# pinheader.net
KiCad netlist of a schematic drawn in Altium Designer
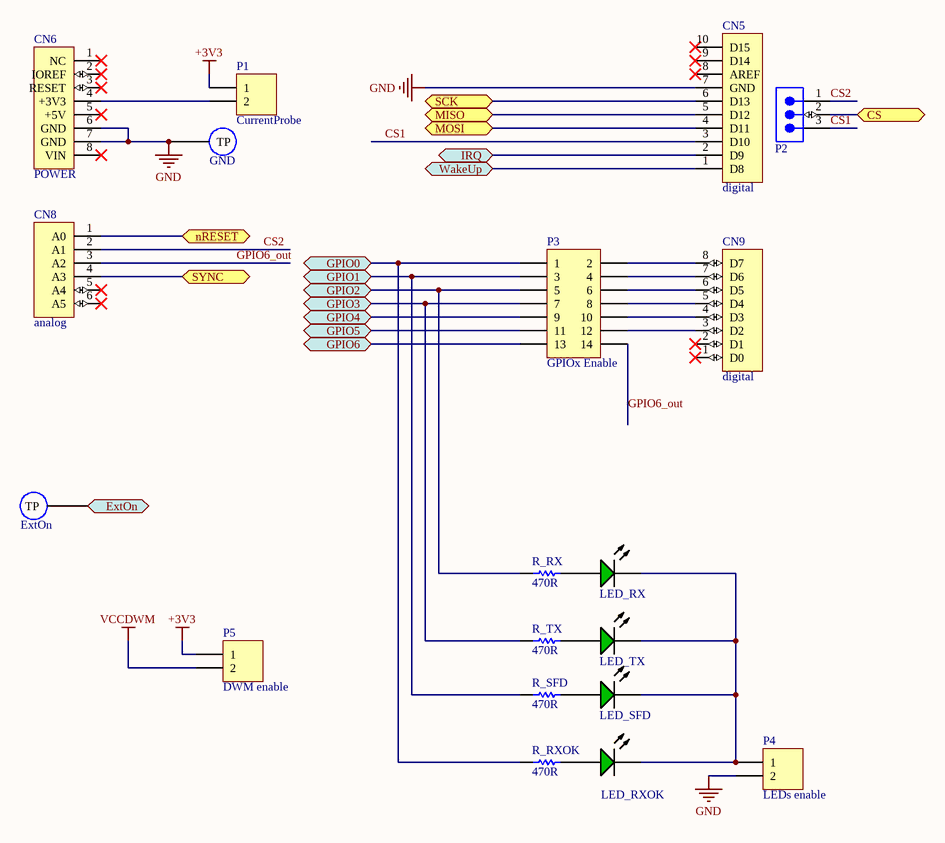
[diagram p0: pinheader.SchDoc]

(export (version "E")
  (design (tool "Eeschema 10.0.6"))
  (components
    (comp (ref "CN5")
      (value "digital")
      (footprint "HDR1X10")
      (description "Header, 10-Pin")
      (fields (field (name "PUBLISHER") "Altium Limited"))
      (libsource (lib "Miscellaneous Connectors") (part "Header 10"))
    )
    (comp (ref "CN6")
      (value "POWER")
      (footprint "HDR1X8")
      (description "Header, 8-Pin")
      (fields (field (name "PUBLISHER") "Altium Limited"))
      (libsource (lib "") (part "Header 8_1"))
    )
    (comp (ref "CN8")
      (value "analog")
      (footprint "HDR1X6")
      (description "Header, 6-Pin")
      (fields (field (name "PUBLISHER") "Altium Limited"))
      (libsource (lib "Miscellaneous Connectors") (part "Header 6"))
    )
    (comp (ref "CN9")
      (value "digital")
      (footprint "HDR1X8")
      (description "Header, 8-Pin")
      (fields (field (name "PUBLISHER") "Altium Limited"))
      (libsource (lib "Miscellaneous Connectors") (part "Header 8"))
    )
    (comp (ref "ExtOn")
      (value "Component_1")
      (footprint "KSTN-5000")
      (description "test point")
      (libsource (lib "testpoint") (part "Component_1"))
    )
    (comp (ref "GND")
      (value "Component_1")
      (footprint "KSTN-5000")
      (description "test point")
      (libsource (lib "testpoint") (part "Component_1"))
    )
    (comp (ref "LED_RX")
      (value "APG1608CGKC/T")
      (footprint "KING-LED0603-25-GREEN_V")
      (description "LED, SMT, 0603(1608), 0.25mm Thickness, Green")
      (libsource (lib "Altium Content Vault") (part "CMP-0239-00001-1"))
    )
    (comp (ref "LED_RXOK")
      (value "APG1608CGKC/T")
      (footprint "KING-LED0603-25-GREEN_V")
      (description "LED, SMT, 0603(1608), 0.25mm Thickness, Green")
      (libsource (lib "Altium Content Vault") (part "CMP-0239-00001-1"))
    )
    (comp (ref "LED_SFD")
      (value "APG1608CGKC/T")
      (footprint "KING-LED0603-25-GREEN_V")
      (description "LED, SMT, 0603(1608), 0.25mm Thickness, Green")
      (libsource (lib "Altium Content Vault") (part "CMP-0239-00001-1"))
    )
    (comp (ref "LED_TX")
      (value "APG1608CGKC/T")
      (footprint "KING-LED0603-25-GREEN_V")
      (description "LED, SMT, 0603(1608), 0.25mm Thickness, Green")
      (libsource (lib "Altium Content Vault") (part "CMP-0239-00001-1"))
    )
    (comp (ref "P1")
      (value "CurrentProbe")
      (footprint "HDR1X2H")
      (description "Header, 2-Pin, Right Angle")
      (fields (field (name "PUBLISHER") "Altium Limited"))
      (libsource (lib "Miscellaneous Connectors") (part "Header 2H"))
    )
    (comp (ref "P2")
      (value "Through-hole")
      (footprint "SMTC-MTSW-103-08-X-S-229-RA")
      (fields (field (name "MANUFACTURER") "Samtec") (field (name "PARTNUMBER") "MTSW-103-08-G-S-229-RA"))
      (libsource (lib "Altium Content Vault") (part "CMP-1024-00100-1"))
    )
    (comp (ref "P3")
      (value "GPIOx Enable")
      (footprint "HDR2X7")
      (description "Header, 7-Pin, Dual row")
      (fields (field (name "PUBLISHER") "Altium Limited"))
      (libsource (lib "Miscellaneous Connectors") (part "Header 7X2"))
    )
    (comp (ref "P4")
      (value "LEDs enable")
      (footprint "HDR1X2")
      (description "Header, 2-Pin")
      (fields (field (name "PUBLISHER") "Altium Limited"))
      (libsource (lib "Miscellaneous Connectors") (part "Header 2"))
    )
    (comp (ref "P5")
      (value "DWM enable")
      (footprint "HDR1X2")
      (description "Header, 2-Pin")
      (fields (field (name "PUBLISHER") "Altium Limited"))
      (libsource (lib "Miscellaneous Connectors") (part "Header 2"))
    )
    (comp (ref "R_RX")
      (value "470R")
      (footprint "RESC0603(1608)_L")
      (description "470R 0.1W 1% 0603 (1608 Metric)  SMD")
      (fields (field (name "POWER") "0.1 W") (field (name "TOLERANCE") "1 %"))
      (libsource (lib "Altium Content Vault") (part "RES"))
    )
    (comp (ref "R_RXOK")
      (value "470R")
      (footprint "RESC0603(1608)_L")
      (description "470R 0.1W 1% 0603 (1608 Metric)  SMD")
      (fields (field (name "POWER") "0.1 W") (field (name "TOLERANCE") "1 %"))
      (libsource (lib "Altium Content Vault") (part "RES"))
    )
    (comp (ref "R_SFD")
      (value "470R")
      (footprint "RESC0603(1608)_L")
      (description "470R 0.1W 1% 0603 (1608 Metric)  SMD")
      (fields (field (name "POWER") "0.1 W") (field (name "TOLERANCE") "1 %"))
      (libsource (lib "Altium Content Vault") (part "RES"))
    )
    (comp (ref "R_TX")
      (value "470R")
      (footprint "RESC0603(1608)_L")
      (description "470R 0.1W 1% 0603 (1608 Metric)  SMD")
      (fields (field (name "POWER") "0.1 W") (field (name "TOLERANCE") "1 %"))
      (libsource (lib "Altium Content Vault") (part "RES"))
    )
  )
  (nets
    (net (code "1") (name "+3V3") (class "Default")
      (node (ref "P1") (pin "1") (pinfunction "1_1") (pintype "passive"))
      (node (ref "P5") (pin "1") (pinfunction "1_1") (pintype "passive"))
    )
    (net (code "2") (name "/CS") (class "Default")
      (node (ref "P2") (pin "2") (pinfunction "2_2") (pintype "bidirectional"))
    )
    (net (code "3") (name "/CS1") (class "Default")
      (node (ref "CN5") (pin "3") (pinfunction "D10_3") (pintype "passive"))
      (node (ref "P2") (pin "3") (pinfunction "3_3") (pintype "passive"))
    )
    (net (code "4") (name "/CS2") (class "Default")
      (node (ref "CN8") (pin "2") (pinfunction "A1_2") (pintype "passive"))
      (node (ref "P2") (pin "1") (pinfunction "1_1") (pintype "passive"))
    )
    (net (code "5") (name "/ExtOn") (class "Default")
      (node (ref "ExtOn") (pin "1") (pinfunction "TP_1") (pintype "passive"))
    )
    (net (code "6") (name "/GPIO0") (class "Default")
      (node (ref "P3") (pin "1") (pinfunction "1_1") (pintype "passive"))
      (node (ref "R_RXOK") (pin "1") (pinfunction "1_1") (pintype "passive"))
    )
    (net (code "7") (name "/GPIO1") (class "Default")
      (node (ref "P3") (pin "3") (pinfunction "3_3") (pintype "passive"))
      (node (ref "R_SFD") (pin "1") (pinfunction "1_1") (pintype "passive"))
    )
    (net (code "8") (name "/GPIO2") (class "Default")
      (node (ref "P3") (pin "5") (pinfunction "5_5") (pintype "passive"))
      (node (ref "R_RX") (pin "1") (pinfunction "1_1") (pintype "passive"))
    )
    (net (code "9") (name "/GPIO3") (class "Default")
      (node (ref "P3") (pin "7") (pinfunction "7_7") (pintype "passive"))
      (node (ref "R_TX") (pin "1") (pinfunction "1_1") (pintype "passive"))
    )
    (net (code "10") (name "/GPIO4") (class "Default")
      (node (ref "P3") (pin "9") (pinfunction "9_9") (pintype "passive"))
    )
    (net (code "11") (name "/GPIO5") (class "Default")
      (node (ref "P3") (pin "11") (pinfunction "11_11") (pintype "passive"))
    )
    (net (code "12") (name "/GPIO6") (class "Default")
      (node (ref "P3") (pin "13") (pinfunction "13_13") (pintype "passive"))
    )
    (net (code "13") (name "/GPIO6_out") (class "Default")
      (node (ref "CN8") (pin "3") (pinfunction "A2_3") (pintype "passive"))
      (node (ref "P3") (pin "14") (pinfunction "14_14") (pintype "passive"))
    )
    (net (code "14") (name "/IRQ") (class "Default")
      (node (ref "CN5") (pin "2") (pinfunction "D9_2") (pintype "passive"))
    )
    (net (code "15") (name "/MISO") (class "Default")
      (node (ref "CN5") (pin "5") (pinfunction "D12_5") (pintype "passive"))
    )
    (net (code "16") (name "/MOSI") (class "Default")
      (node (ref "CN5") (pin "4") (pinfunction "D11_4") (pintype "passive"))
    )
    (net (code "17") (name "/SCK") (class "Default")
      (node (ref "CN5") (pin "6") (pinfunction "D13_6") (pintype "passive"))
    )
    (net (code "18") (name "/SYNC") (class "Default")
      (node (ref "CN8") (pin "4") (pinfunction "A3_4") (pintype "passive"))
    )
    (net (code "19") (name "/WakeUp") (class "Default")
      (node (ref "CN5") (pin "1") (pinfunction "D8_1") (pintype "passive"))
    )
    (net (code "20") (name "/nRESET") (class "Default")
      (node (ref "CN8") (pin "1") (pinfunction "A0_1") (pintype "passive"))
    )
    (net (code "21") (name "GND") (class "Default")
      (node (ref "CN5") (pin "7") (pinfunction "GND_7") (pintype "passive"))
      (node (ref "CN6") (pin "6") (pinfunction "GND_6") (pintype "passive"))
      (node (ref "CN6") (pin "7") (pinfunction "GND_7") (pintype "passive"))
      (node (ref "GND") (pin "1") (pinfunction "TP_1") (pintype "passive"))
      (node (ref "P4") (pin "2") (pinfunction "2_2") (pintype "passive"))
    )
    (net (code "22") (name "Net-(CN6-+3V3)") (class "Default")
      (node (ref "CN6") (pin "4") (pinfunction "+3V3_4") (pintype "power_in"))
      (node (ref "P1") (pin "2") (pinfunction "2_2") (pintype "passive"))
    )
    (net (code "23") (name "Net-(CN9-D2)") (class "Default")
      (node (ref "CN9") (pin "3") (pinfunction "D2_3") (pintype "bidirectional"))
      (node (ref "P3") (pin "12") (pinfunction "12_12") (pintype "passive"))
    )
    (net (code "24") (name "Net-(CN9-D3)") (class "Default")
      (node (ref "CN9") (pin "4") (pinfunction "D3_4") (pintype "bidirectional"))
      (node (ref "P3") (pin "10") (pinfunction "10_10") (pintype "passive"))
    )
    (net (code "25") (name "Net-(CN9-D4)") (class "Default")
      (node (ref "CN9") (pin "5") (pinfunction "D4_5") (pintype "bidirectional"))
      (node (ref "P3") (pin "8") (pinfunction "8_8") (pintype "passive"))
    )
    (net (code "26") (name "Net-(CN9-D5)") (class "Default")
      (node (ref "CN9") (pin "6") (pinfunction "D5_6") (pintype "bidirectional"))
      (node (ref "P3") (pin "6") (pinfunction "6_6") (pintype "passive"))
    )
    (net (code "27") (name "Net-(CN9-D6)") (class "Default")
      (node (ref "CN9") (pin "7") (pinfunction "D6_7") (pintype "bidirectional"))
      (node (ref "P3") (pin "4") (pinfunction "4_4") (pintype "passive"))
    )
    (net (code "28") (name "Net-(CN9-D7)") (class "Default")
      (node (ref "CN9") (pin "8") (pinfunction "D7_8") (pintype "bidirectional"))
      (node (ref "P3") (pin "2") (pinfunction "2_2") (pintype "passive"))
    )
    (net (code "29") (name "Net-(LED_RX-A)") (class "Default")
      (node (ref "LED_RX") (pin "1") (pinfunction "A_1") (pintype "passive"))
      (node (ref "R_RX") (pin "2") (pinfunction "2_2") (pintype "passive"))
    )
    (net (code "30") (name "Net-(LED_RX-K)") (class "Default")
      (node (ref "LED_RX") (pin "2") (pinfunction "K_2") (pintype "passive"))
      (node (ref "LED_RXOK") (pin "2") (pinfunction "K_2") (pintype "passive"))
      (node (ref "LED_SFD") (pin "2") (pinfunction "K_2") (pintype "passive"))
      (node (ref "LED_TX") (pin "2") (pinfunction "K_2") (pintype "passive"))
      (node (ref "P4") (pin "1") (pinfunction "1_1") (pintype "passive"))
    )
    (net (code "31") (name "Net-(LED_RXOK-A)") (class "Default")
      (node (ref "LED_RXOK") (pin "1") (pinfunction "A_1") (pintype "passive"))
      (node (ref "R_RXOK") (pin "2") (pinfunction "2_2") (pintype "passive"))
    )
    (net (code "32") (name "Net-(LED_SFD-A)") (class "Default")
      (node (ref "LED_SFD") (pin "1") (pinfunction "A_1") (pintype "passive"))
      (node (ref "R_SFD") (pin "2") (pinfunction "2_2") (pintype "passive"))
    )
    (net (code "33") (name "Net-(LED_TX-A)") (class "Default")
      (node (ref "LED_TX") (pin "1") (pinfunction "A_1") (pintype "passive"))
      (node (ref "R_TX") (pin "2") (pinfunction "2_2") (pintype "passive"))
    )
    (net (code "34") (name "VCCDWM") (class "Default")
      (node (ref "P5") (pin "2") (pinfunction "2_2") (pintype "passive"))
    )
    (net (code "35") (name "unconnected-(CN5-AREF-Pad8)") (class "Default")
      (node (ref "CN5") (pin "8") (pinfunction "AREF_8") (pintype "passive+no_connect"))
    )
    (net (code "36") (name "unconnected-(CN5-D14-Pad9)") (class "Default")
      (node (ref "CN5") (pin "9") (pinfunction "D14_9") (pintype "passive+no_connect"))
    )
    (net (code "37") (name "unconnected-(CN5-D15-Pad10)") (class "Default")
      (node (ref "CN5") (pin "10") (pinfunction "D15_10") (pintype "passive+no_connect"))
    )
    (net (code "38") (name "unconnected-(CN6-+5V-Pad5)") (class "Default")
      (node (ref "CN6") (pin "5") (pinfunction "+5V_5") (pintype "power_in+no_connect"))
    )
    (net (code "39") (name "unconnected-(CN6-IOREF-Pad2)") (class "Default")
      (node (ref "CN6") (pin "2") (pinfunction "IOREF_2") (pintype "bidirectional+no_connect"))
    )
    (net (code "40") (name "unconnected-(CN6-NC-Pad1)") (class "Default")
      (node (ref "CN6") (pin "1") (pinfunction "NC_1") (pintype "passive+no_connect"))
    )
    (net (code "41") (name "unconnected-(CN6-RESET-Pad3)") (class "Default")
      (node (ref "CN6") (pin "3") (pinfunction "RESET_3") (pintype "bidirectional+no_connect"))
    )
    (net (code "42") (name "unconnected-(CN6-VIN-Pad8)") (class "Default")
      (node (ref "CN6") (pin "8") (pinfunction "VIN_8") (pintype "passive+no_connect"))
    )
    (net (code "43") (name "unconnected-(CN8-A4-Pad5)") (class "Default")
      (node (ref "CN8") (pin "5") (pinfunction "A4_5") (pintype "bidirectional+no_connect"))
    )
    (net (code "44") (name "unconnected-(CN8-A5-Pad6)") (class "Default")
      (node (ref "CN8") (pin "6") (pinfunction "A5_6") (pintype "bidirectional+no_connect"))
    )
    (net (code "45") (name "unconnected-(CN9-D0-Pad1)") (class "Default")
      (node (ref "CN9") (pin "1") (pinfunction "D0_1") (pintype "bidirectional+no_connect"))
    )
    (net (code "46") (name "unconnected-(CN9-D1-Pad2)") (class "Default")
      (node (ref "CN9") (pin "2") (pinfunction "D1_2") (pintype "bidirectional+no_connect"))
    )
  )
)
